# Shema.net
KiCad netlist of a schematic drawn in Altium Designer
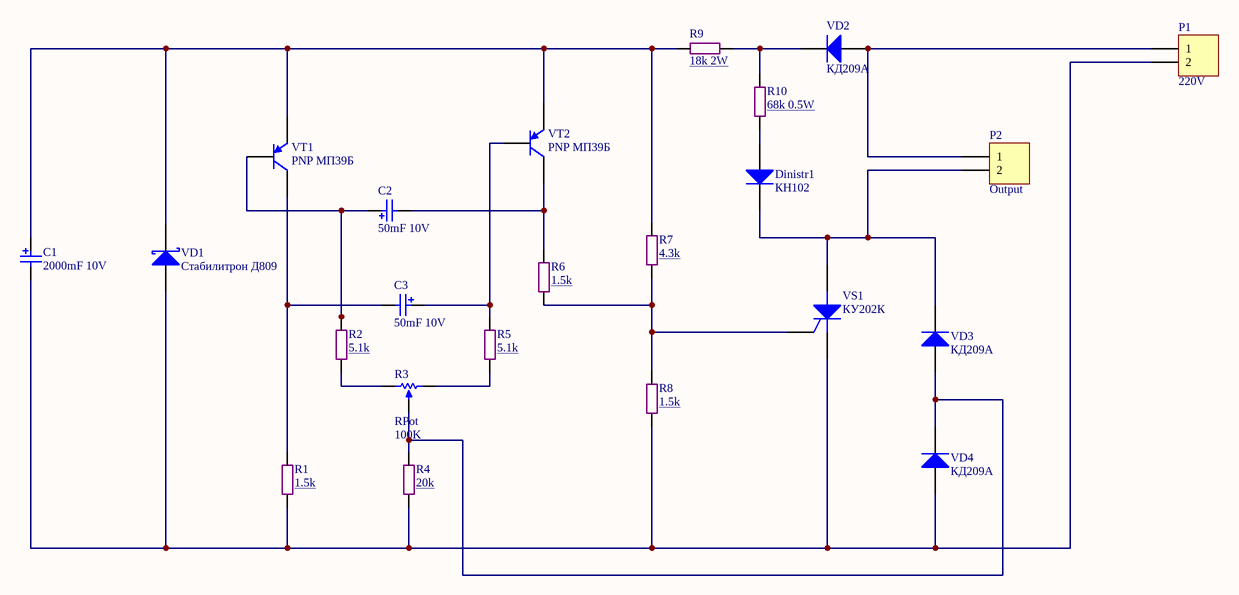
[diagram p0: Shema.SchDoc]

(export (version "E")
  (design (tool "Eeschema 10.0.6"))
  (components
    (comp (ref "C1")
      (value "2000mF 10V")
      (footprint "bj Lib:Cap p7.62mm D16mm (4p)")
      (description "Capacitor Electrolitic")
      (libsource (lib "bj Lib") (part "Cap Cylinder"))
    )
    (comp (ref "C2")
      (value "50mF 10V")
      (footprint "bj Lib:Cap p2.54mm D5mm (2p)")
      (description "Capacitor Electrolitic")
      (libsource (lib "bj Lib") (part "Cap Cylinder"))
    )
    (comp (ref "C3")
      (value "50mF 10V")
      (footprint "bj Lib:Cap p2.54mm D5mm (2p)")
      (description "Capacitor Electrolitic")
      (libsource (lib "bj Lib") (part "Cap Cylinder"))
    )
    (comp (ref "Dinistr1")
      (value "КН102")
      (footprint "DO-41")
      (description "1 Amp General Purpose Rectifier")
      (fields (field (name "PUBLISHER") "Altium Limited"))
      (libsource (lib "Miscellaneous Devices") (part "Diode 1N4002"))
    )
    (comp (ref "P1")
      (value "220V")
      (footprint "HDR1X2")
      (description "Header, 2-Pin")
      (fields (field (name "PUBLISHER") "Altium Limited"))
      (libsource (lib "Miscellaneous Connectors") (part "Header 2"))
    )
    (comp (ref "P2")
      (value "Output")
      (footprint "HDR1X2")
      (description "Header, 2-Pin")
      (fields (field (name "PUBLISHER") "Altium Limited"))
      (libsource (lib "Miscellaneous Connectors") (part "Header 2"))
    )
    (comp (ref "R1")
      (value "1.5k")
      (footprint "bj Lib:Res p7.62")
      (libsource (lib "bj Lib") (part "Resistor"))
    )
    (comp (ref "R2")
      (value "5.1k")
      (footprint "bj Lib:Res p7.62")
      (libsource (lib "bj Lib") (part "Resistor"))
    )
    (comp (ref "R3")
      (value "RPot")
      (footprint "VR5")
      (description "Potentiometer")
      (fields (field (name "ALTIUM_VALUE") "100K") (field (name "PUBLISHER") "Altium Limited"))
      (libsource (lib "Miscellaneous Devices") (part "RPot"))
    )
    (comp (ref "R4")
      (value "20k")
      (footprint "bj Lib:Res p7.62")
      (libsource (lib "bj Lib") (part "Resistor"))
    )
    (comp (ref "R5")
      (value "5.1k")
      (footprint "bj Lib:Res p7.62")
      (libsource (lib "bj Lib") (part "Resistor"))
    )
    (comp (ref "R6")
      (value "1.5k")
      (footprint "bj Lib:Res p7.62")
      (libsource (lib "bj Lib") (part "Resistor"))
    )
    (comp (ref "R7")
      (value "4.3k")
      (footprint "bj Lib:Res p7.62")
      (libsource (lib "bj Lib") (part "Resistor"))
    )
    (comp (ref "R8")
      (value "1.5k")
      (footprint "bj Lib:Res p7.62")
      (libsource (lib "bj Lib") (part "Resistor"))
    )
    (comp (ref "R9")
      (value "18k 2W")
      (footprint "bj Lib:Res p7.62")
      (libsource (lib "bj Lib") (part "Resistor"))
    )
    (comp (ref "R10")
      (value "68k 0.5W")
      (footprint "bj Lib:Res p7.62")
      (libsource (lib "bj Lib") (part "Resistor"))
    )
    (comp (ref "VD1")
      (value "Стабилитрон Д809")
      (footprint "DO-204AL")
      (description "Schottky Rectifier")
      (fields (field (name "PUBLISHER") "Altium Limited"))
      (libsource (lib "Miscellaneous Devices") (part "Diode 11DQ03"))
    )
    (comp (ref "VD2")
      (value "КД209А")
      (footprint "DO-41")
      (description "1 Amp General Purpose Rectifier")
      (fields (field (name "PUBLISHER") "Altium Limited"))
      (libsource (lib "Miscellaneous Devices") (part "Diode 1N4002"))
    )
    (comp (ref "VD3")
      (value "КД209А")
      (footprint "DO-41")
      (description "1 Amp General Purpose Rectifier")
      (fields (field (name "PUBLISHER") "Altium Limited"))
      (libsource (lib "Miscellaneous Devices") (part "Diode 1N4002"))
    )
    (comp (ref "VD4")
      (value "КД209А")
      (footprint "DO-41")
      (description "1 Amp General Purpose Rectifier")
      (fields (field (name "PUBLISHER") "Altium Limited"))
      (libsource (lib "Miscellaneous Devices") (part "Diode 1N4002"))
    )
    (comp (ref "VS1")
      (value "КУ202К")
      (footprint "TO-220-AB")
      (description "Silicon Controlled Rectifier")
      (fields (field (name "PUBLISHER") "Altium Limited"))
      (libsource (lib "Miscellaneous Devices") (part "SCR"))
    )
    (comp (ref "VT1")
      (value "PNP МП39Б")
      (footprint "SOT-23B_N")
      (description "PNP Bipolar Transistor")
      (fields (field (name "PUBLISHER") "Altium Limited"))
      (libsource (lib "Miscellaneous Devices") (part "PNP"))
    )
    (comp (ref "VT2")
      (value "PNP МП39Б")
      (footprint "SOT-23B_N")
      (description "PNP Bipolar Transistor")
      (fields (field (name "PUBLISHER") "Altium Limited"))
      (libsource (lib "Miscellaneous Devices") (part "PNP"))
    )
  )
  (nets
    (net (code "1") (name "Net-(Dinistr1-A)") (class "Default")
      (node (ref "Dinistr1") (pin "1") (pinfunction "A_1") (pintype "passive"))
      (node (ref "R10") (pin "2") (pinfunction "2_2") (pintype "passive"))
    )
    (net (code "2") (name "Net-(Dinistr1-K)") (class "Default")
      (node (ref "Dinistr1") (pin "2") (pinfunction "K_2") (pintype "passive"))
      (node (ref "P2") (pin "2") (pinfunction "2_2") (pintype "passive"))
      (node (ref "VD3") (pin "2") (pinfunction "K_2") (pintype "passive"))
      (node (ref "VS1") (pin "1") (pinfunction "A_1") (pintype "passive"))
    )
    (net (code "3") (name "Net-(R3-BOT)") (class "Default")
      (node (ref "R3") (pin "2") (pinfunction "BOT_2") (pintype "passive"))
      (node (ref "R5") (pin "1") (pinfunction "1_1") (pintype "passive"))
    )
    (net (code "4") (name "Net-(R3-TAP)") (class "Default")
      (node (ref "R3") (pin "3") (pinfunction "TAP_3") (pintype "passive"))
      (node (ref "R4") (pin "2") (pinfunction "2_2") (pintype "passive"))
      (node (ref "VD3") (pin "1") (pinfunction "A_1") (pintype "passive"))
      (node (ref "VD4") (pin "2") (pinfunction "K_2") (pintype "passive"))
    )
    (net (code "5") (name "Net-(R3-TOP)") (class "Default")
      (node (ref "R2") (pin "1") (pinfunction "1_1") (pintype "passive"))
      (node (ref "R3") (pin "1") (pinfunction "TOP_1") (pintype "passive"))
    )
    (net (code "6") (name "Net-(VD1-A)") (class "Default")
      (node (ref "C1") (pin "2") (pinfunction "2_2") (pintype "passive"))
      (node (ref "P1") (pin "2") (pinfunction "2_2") (pintype "passive"))
      (node (ref "R1") (pin "1") (pinfunction "1_1") (pintype "passive"))
      (node (ref "R4") (pin "1") (pinfunction "1_1") (pintype "passive"))
      (node (ref "R8") (pin "1") (pinfunction "1_1") (pintype "passive"))
      (node (ref "VD1") (pin "1") (pinfunction "A_1") (pintype "passive"))
      (node (ref "VD4") (pin "1") (pinfunction "A_1") (pintype "passive"))
      (node (ref "VS1") (pin "3") (pinfunction "K_3") (pintype "passive"))
    )
    (net (code "7") (name "Net-(VD1-K)") (class "Default")
      (node (ref "C1") (pin "1") (pinfunction "1_1") (pintype "passive"))
      (node (ref "R7") (pin "2") (pinfunction "2_2") (pintype "passive"))
      (node (ref "R9") (pin "2") (pinfunction "2_2") (pintype "passive"))
      (node (ref "VD1") (pin "2") (pinfunction "K_2") (pintype "passive"))
      (node (ref "VT1") (pin "3") (pinfunction "E_3") (pintype "passive"))
      (node (ref "VT2") (pin "3") (pinfunction "E_3") (pintype "passive"))
    )
    (net (code "8") (name "Net-(VD2-A)") (class "Default")
      (node (ref "P1") (pin "1") (pinfunction "1_1") (pintype "passive"))
      (node (ref "P2") (pin "1") (pinfunction "1_1") (pintype "passive"))
      (node (ref "VD2") (pin "1") (pinfunction "A_1") (pintype "passive"))
    )
    (net (code "9") (name "Net-(VD2-K)") (class "Default")
      (node (ref "R10") (pin "1") (pinfunction "1_1") (pintype "passive"))
      (node (ref "R9") (pin "1") (pinfunction "1_1") (pintype "passive"))
      (node (ref "VD2") (pin "2") (pinfunction "K_2") (pintype "passive"))
    )
    (net (code "10") (name "Net-(VS1-G)") (class "Default")
      (node (ref "R6") (pin "1") (pinfunction "1_1") (pintype "passive"))
      (node (ref "R7") (pin "1") (pinfunction "1_1") (pintype "passive"))
      (node (ref "R8") (pin "2") (pinfunction "2_2") (pintype "passive"))
      (node (ref "VS1") (pin "2") (pinfunction "G_2") (pintype "passive"))
    )
    (net (code "11") (name "Net-(VT1-B)") (class "Default")
      (node (ref "C2") (pin "1") (pinfunction "1_1") (pintype "passive"))
      (node (ref "R2") (pin "2") (pinfunction "2_2") (pintype "passive"))
      (node (ref "VT1") (pin "2") (pinfunction "B_2") (pintype "passive"))
    )
    (net (code "12") (name "Net-(VT1-C)") (class "Default")
      (node (ref "C3") (pin "2") (pinfunction "2_2") (pintype "passive"))
      (node (ref "R1") (pin "2") (pinfunction "2_2") (pintype "passive"))
      (node (ref "VT1") (pin "1") (pinfunction "C_1") (pintype "passive"))
    )
    (net (code "13") (name "Net-(VT2-B)") (class "Default")
      (node (ref "C3") (pin "1") (pinfunction "1_1") (pintype "passive"))
      (node (ref "R5") (pin "2") (pinfunction "2_2") (pintype "passive"))
      (node (ref "VT2") (pin "2") (pinfunction "B_2") (pintype "passive"))
    )
    (net (code "14") (name "Net-(VT2-C)") (class "Default")
      (node (ref "C2") (pin "2") (pinfunction "2_2") (pintype "passive"))
      (node (ref "R6") (pin "2") (pinfunction "2_2") (pintype "passive"))
      (node (ref "VT2") (pin "1") (pinfunction "C_1") (pintype "passive"))
    )
  )
)
